# Orbiter_V3.net
KiCad netlist of a schematic drawn in EAGLE
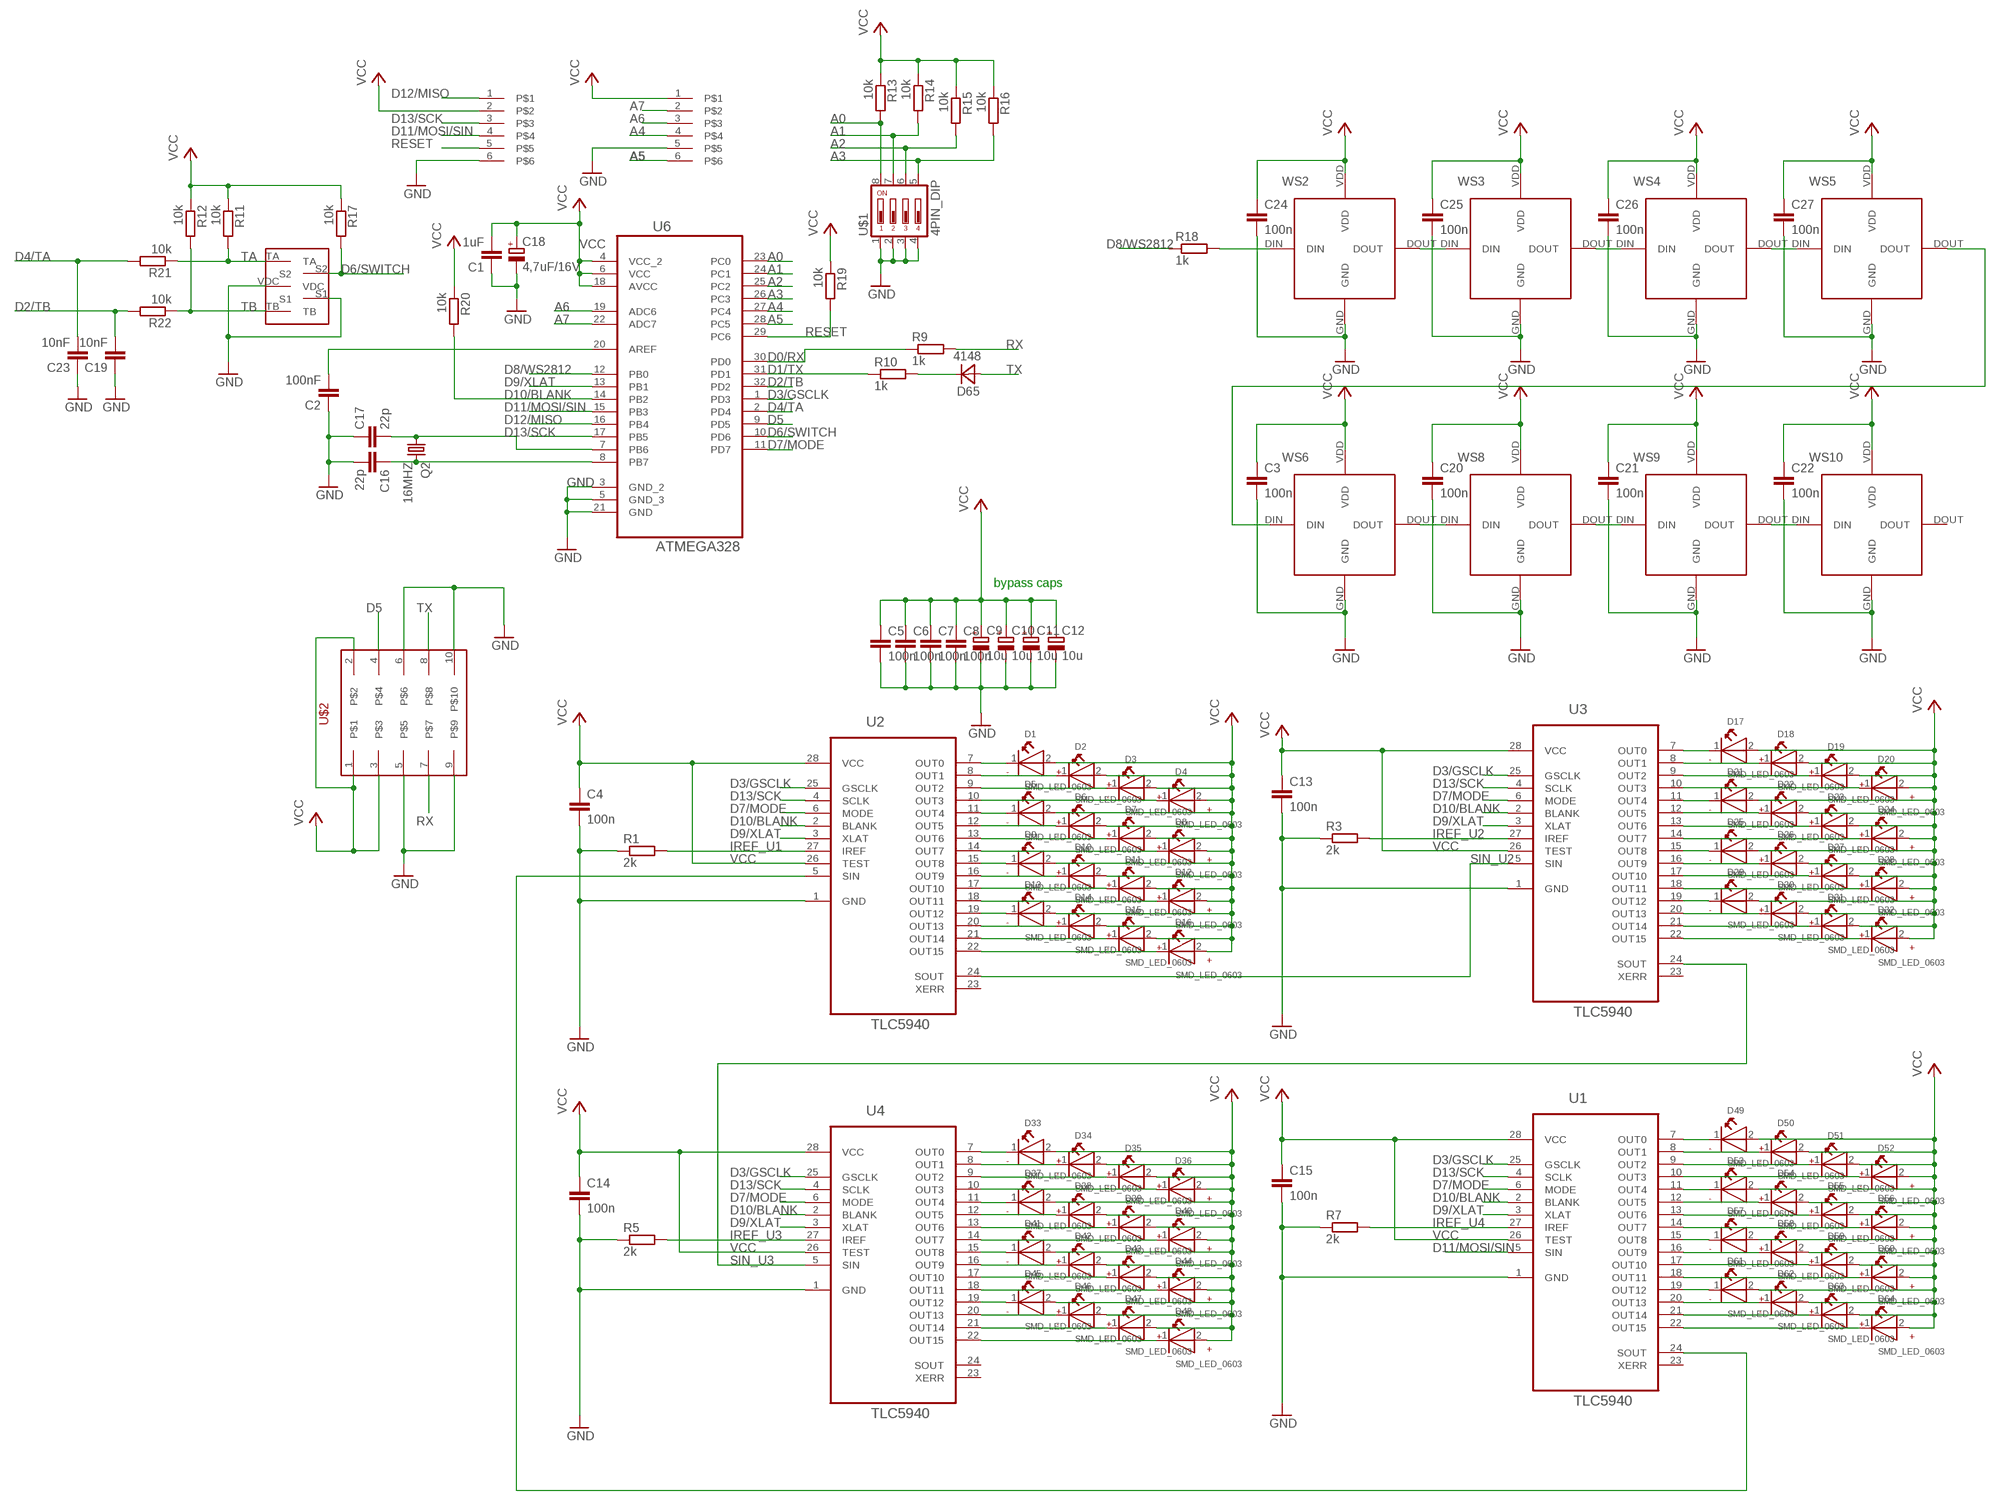
[diagram p0: schematic, sheet 1]

(export (version "E")
  (design (tool "Eeschema 10.0.6"))
  (components
    (comp (ref "C1")
      (value "1uF")
      (footprint "eagle-import:C0603")
      (libsource (lib "eagle-import") (part "KONDENSATOR_0603"))
    )
    (comp (ref "C2")
      (value "100nF")
      (footprint "eagle-import:C0603")
      (libsource (lib "eagle-import") (part "KONDENSATOR_0603"))
    )
    (comp (ref "C3")
      (value "100n")
      (footprint "eagle-import:C0603")
      (libsource (lib "eagle-import") (part "KONDENSATOR_0603"))
    )
    (comp (ref "C4")
      (value "100n")
      (footprint "eagle-import:C0603")
      (libsource (lib "eagle-import") (part "KONDENSATOR_0603"))
    )
    (comp (ref "C5")
      (value "100n")
      (footprint "eagle-import:C0603")
      (libsource (lib "eagle-import") (part "KONDENSATOR_0603"))
    )
    (comp (ref "C6")
      (value "100n")
      (footprint "eagle-import:C0603")
      (libsource (lib "eagle-import") (part "KONDENSATOR_0603"))
    )
    (comp (ref "C7")
      (value "100n")
      (footprint "eagle-import:C0603")
      (libsource (lib "eagle-import") (part "KONDENSATOR_0603"))
    )
    (comp (ref "C8")
      (value "100n")
      (footprint "eagle-import:C0603")
      (libsource (lib "eagle-import") (part "KONDENSATOR_0603"))
    )
    (comp (ref "C9")
      (value "10u")
      (footprint "eagle-import:153CLV-0605")
      (libsource (lib "eagle-import") (part "SMD_ELCTROLYTIC"))
    )
    (comp (ref "C10")
      (value "10u")
      (footprint "eagle-import:153CLV-0605")
      (libsource (lib "eagle-import") (part "SMD_ELCTROLYTIC"))
    )
    (comp (ref "C11")
      (value "10u")
      (footprint "eagle-import:153CLV-0605")
      (libsource (lib "eagle-import") (part "SMD_ELCTROLYTIC"))
    )
    (comp (ref "C12")
      (value "10u")
      (footprint "eagle-import:153CLV-0605")
      (libsource (lib "eagle-import") (part "SMD_ELCTROLYTIC"))
    )
    (comp (ref "C13")
      (value "100n")
      (footprint "eagle-import:C0603")
      (libsource (lib "eagle-import") (part "KONDENSATOR_0603"))
    )
    (comp (ref "C14")
      (value "100n")
      (footprint "eagle-import:C0603")
      (libsource (lib "eagle-import") (part "KONDENSATOR_0603"))
    )
    (comp (ref "C15")
      (value "100n")
      (footprint "eagle-import:C0603")
      (libsource (lib "eagle-import") (part "KONDENSATOR_0603"))
    )
    (comp (ref "C16")
      (value "22p")
      (footprint "eagle-import:C0603")
      (libsource (lib "eagle-import") (part "KONDENSATOR_0603"))
    )
    (comp (ref "C17")
      (value "22p")
      (footprint "eagle-import:C0603")
      (libsource (lib "eagle-import") (part "KONDENSATOR_0603"))
    )
    (comp (ref "C18")
      (value "4,7uF/16V")
      (footprint "eagle-import:153CLV-0605")
      (libsource (lib "eagle-import") (part "SMD_ELCTROLYTIC"))
    )
    (comp (ref "C19")
      (value "10nF")
      (footprint "eagle-import:C0603")
      (libsource (lib "eagle-import") (part "KONDENSATOR_0603"))
    )
    (comp (ref "C20")
      (value "100n")
      (footprint "eagle-import:C0603")
      (libsource (lib "eagle-import") (part "KONDENSATOR_0603"))
    )
    (comp (ref "C21")
      (value "100n")
      (footprint "eagle-import:C0603")
      (libsource (lib "eagle-import") (part "KONDENSATOR_0603"))
    )
    (comp (ref "C22")
      (value "100n")
      (footprint "eagle-import:C0603")
      (libsource (lib "eagle-import") (part "KONDENSATOR_0603"))
    )
    (comp (ref "C23")
      (value "10nF")
      (footprint "eagle-import:C0603")
      (libsource (lib "eagle-import") (part "KONDENSATOR_0603"))
    )
    (comp (ref "C24")
      (value "100n")
      (footprint "eagle-import:C0603")
      (libsource (lib "eagle-import") (part "KONDENSATOR_0603"))
    )
    (comp (ref "C25")
      (value "100n")
      (footprint "eagle-import:C0603")
      (libsource (lib "eagle-import") (part "KONDENSATOR_0603"))
    )
    (comp (ref "C26")
      (value "100n")
      (footprint "eagle-import:C0603")
      (libsource (lib "eagle-import") (part "KONDENSATOR_0603"))
    )
    (comp (ref "C27")
      (value "100n")
      (footprint "eagle-import:C0603")
      (libsource (lib "eagle-import") (part "KONDENSATOR_0603"))
    )
    (comp (ref "D1")
      (value "SMD_LED_0603")
      (footprint "eagle-import:WL-SMCW_0603")
      (libsource (lib "eagle-import") (part "SMD_LED_0603"))
    )
    (comp (ref "D2")
      (value "SMD_LED_0603")
      (footprint "eagle-import:WL-SMCW_0603")
      (libsource (lib "eagle-import") (part "SMD_LED_0603"))
    )
    (comp (ref "D3")
      (value "SMD_LED_0603")
      (footprint "eagle-import:WL-SMCW_0603")
      (libsource (lib "eagle-import") (part "SMD_LED_0603"))
    )
    (comp (ref "D4")
      (value "SMD_LED_0603")
      (footprint "eagle-import:WL-SMCW_0603")
      (libsource (lib "eagle-import") (part "SMD_LED_0603"))
    )
    (comp (ref "D5")
      (value "SMD_LED_0603")
      (footprint "eagle-import:WL-SMCW_0603")
      (libsource (lib "eagle-import") (part "SMD_LED_0603"))
    )
    (comp (ref "D6")
      (value "SMD_LED_0603")
      (footprint "eagle-import:WL-SMCW_0603")
      (libsource (lib "eagle-import") (part "SMD_LED_0603"))
    )
    (comp (ref "D7")
      (value "SMD_LED_0603")
      (footprint "eagle-import:WL-SMCW_0603")
      (libsource (lib "eagle-import") (part "SMD_LED_0603"))
    )
    (comp (ref "D8")
      (value "SMD_LED_0603")
      (footprint "eagle-import:WL-SMCW_0603")
      (libsource (lib "eagle-import") (part "SMD_LED_0603"))
    )
    (comp (ref "D9")
      (value "SMD_LED_0603")
      (footprint "eagle-import:WL-SMCW_0603")
      (libsource (lib "eagle-import") (part "SMD_LED_0603"))
    )
    (comp (ref "D10")
      (value "SMD_LED_0603")
      (footprint "eagle-import:WL-SMCW_0603")
      (libsource (lib "eagle-import") (part "SMD_LED_0603"))
    )
    (comp (ref "D11")
      (value "SMD_LED_0603")
      (footprint "eagle-import:WL-SMCW_0603")
      (libsource (lib "eagle-import") (part "SMD_LED_0603"))
    )
    (comp (ref "D12")
      (value "SMD_LED_0603")
      (footprint "eagle-import:WL-SMCW_0603")
      (libsource (lib "eagle-import") (part "SMD_LED_0603"))
    )
    (comp (ref "D13")
      (value "SMD_LED_0603")
      (footprint "eagle-import:WL-SMCW_0603")
      (libsource (lib "eagle-import") (part "SMD_LED_0603"))
    )
    (comp (ref "D14")
      (value "SMD_LED_0603")
      (footprint "eagle-import:WL-SMCW_0603")
      (libsource (lib "eagle-import") (part "SMD_LED_0603"))
    )
    (comp (ref "D15")
      (value "SMD_LED_0603")
      (footprint "eagle-import:WL-SMCW_0603")
      (libsource (lib "eagle-import") (part "SMD_LED_0603"))
    )
    (comp (ref "D16")
      (value "SMD_LED_0603")
      (footprint "eagle-import:WL-SMCW_0603")
      (libsource (lib "eagle-import") (part "SMD_LED_0603"))
    )
    (comp (ref "D17")
      (value "SMD_LED_0603")
      (footprint "eagle-import:WL-SMCW_0603")
      (libsource (lib "eagle-import") (part "SMD_LED_0603"))
    )
    (comp (ref "D18")
      (value "SMD_LED_0603")
      (footprint "eagle-import:WL-SMCW_0603")
      (libsource (lib "eagle-import") (part "SMD_LED_0603"))
    )
    (comp (ref "D19")
      (value "SMD_LED_0603")
      (footprint "eagle-import:WL-SMCW_0603")
      (libsource (lib "eagle-import") (part "SMD_LED_0603"))
    )
    (comp (ref "D20")
      (value "SMD_LED_0603")
      (footprint "eagle-import:WL-SMCW_0603")
      (libsource (lib "eagle-import") (part "SMD_LED_0603"))
    )
    (comp (ref "D21")
      (value "SMD_LED_0603")
      (footprint "eagle-import:WL-SMCW_0603")
      (libsource (lib "eagle-import") (part "SMD_LED_0603"))
    )
    (comp (ref "D22")
      (value "SMD_LED_0603")
      (footprint "eagle-import:WL-SMCW_0603")
      (libsource (lib "eagle-import") (part "SMD_LED_0603"))
    )
    (comp (ref "D23")
      (value "SMD_LED_0603")
      (footprint "eagle-import:WL-SMCW_0603")
      (libsource (lib "eagle-import") (part "SMD_LED_0603"))
    )
    (comp (ref "D24")
      (value "SMD_LED_0603")
      (footprint "eagle-import:WL-SMCW_0603")
      (libsource (lib "eagle-import") (part "SMD_LED_0603"))
    )
    (comp (ref "D25")
      (value "SMD_LED_0603")
      (footprint "eagle-import:WL-SMCW_0603")
      (libsource (lib "eagle-import") (part "SMD_LED_0603"))
    )
    (comp (ref "D26")
      (value "SMD_LED_0603")
      (footprint "eagle-import:WL-SMCW_0603")
      (libsource (lib "eagle-import") (part "SMD_LED_0603"))
    )
    (comp (ref "D27")
      (value "SMD_LED_0603")
      (footprint "eagle-import:WL-SMCW_0603")
      (libsource (lib "eagle-import") (part "SMD_LED_0603"))
    )
    (comp (ref "D28")
      (value "SMD_LED_0603")
      (footprint "eagle-import:WL-SMCW_0603")
      (libsource (lib "eagle-import") (part "SMD_LED_0603"))
    )
    (comp (ref "D29")
      (value "SMD_LED_0603")
      (footprint "eagle-import:WL-SMCW_0603")
      (libsource (lib "eagle-import") (part "SMD_LED_0603"))
    )
    (comp (ref "D30")
      (value "SMD_LED_0603")
      (footprint "eagle-import:WL-SMCW_0603")
      (libsource (lib "eagle-import") (part "SMD_LED_0603"))
    )
    (comp (ref "D31")
      (value "SMD_LED_0603")
      (footprint "eagle-import:WL-SMCW_0603")
      (libsource (lib "eagle-import") (part "SMD_LED_0603"))
    )
    (comp (ref "D32")
      (value "SMD_LED_0603")
      (footprint "eagle-import:WL-SMCW_0603")
      (libsource (lib "eagle-import") (part "SMD_LED_0603"))
    )
    (comp (ref "D33")
      (value "SMD_LED_0603")
      (footprint "eagle-import:WL-SMCW_0603")
      (libsource (lib "eagle-import") (part "SMD_LED_0603"))
    )
    (comp (ref "D34")
      (value "SMD_LED_0603")
      (footprint "eagle-import:WL-SMCW_0603")
      (libsource (lib "eagle-import") (part "SMD_LED_0603"))
    )
    (comp (ref "D35")
      (value "SMD_LED_0603")
      (footprint "eagle-import:WL-SMCW_0603")
      (libsource (lib "eagle-import") (part "SMD_LED_0603"))
    )
    (comp (ref "D36")
      (value "SMD_LED_0603")
      (footprint "eagle-import:WL-SMCW_0603")
      (libsource (lib "eagle-import") (part "SMD_LED_0603"))
    )
    (comp (ref "D37")
      (value "SMD_LED_0603")
      (footprint "eagle-import:WL-SMCW_0603")
      (libsource (lib "eagle-import") (part "SMD_LED_0603"))
    )
    (comp (ref "D38")
      (value "SMD_LED_0603")
      (footprint "eagle-import:WL-SMCW_0603")
      (libsource (lib "eagle-import") (part "SMD_LED_0603"))
    )
    (comp (ref "D39")
      (value "SMD_LED_0603")
      (footprint "eagle-import:WL-SMCW_0603")
      (libsource (lib "eagle-import") (part "SMD_LED_0603"))
    )
    (comp (ref "D40")
      (value "SMD_LED_0603")
      (footprint "eagle-import:WL-SMCW_0603")
      (libsource (lib "eagle-import") (part "SMD_LED_0603"))
    )
    (comp (ref "D41")
      (value "SMD_LED_0603")
      (footprint "eagle-import:WL-SMCW_0603")
      (libsource (lib "eagle-import") (part "SMD_LED_0603"))
    )
    (comp (ref "D42")
      (value "SMD_LED_0603")
      (footprint "eagle-import:WL-SMCW_0603")
      (libsource (lib "eagle-import") (part "SMD_LED_0603"))
    )
    (comp (ref "D43")
      (value "SMD_LED_0603")
      (footprint "eagle-import:WL-SMCW_0603")
      (libsource (lib "eagle-import") (part "SMD_LED_0603"))
    )
    (comp (ref "D44")
      (value "SMD_LED_0603")
      (footprint "eagle-import:WL-SMCW_0603")
      (libsource (lib "eagle-import") (part "SMD_LED_0603"))
    )
    (comp (ref "D45")
      (value "SMD_LED_0603")
      (footprint "eagle-import:WL-SMCW_0603")
      (libsource (lib "eagle-import") (part "SMD_LED_0603"))
    )
    (comp (ref "D46")
      (value "SMD_LED_0603")
      (footprint "eagle-import:WL-SMCW_0603")
      (libsource (lib "eagle-import") (part "SMD_LED_0603"))
    )
    (comp (ref "D47")
      (value "SMD_LED_0603")
      (footprint "eagle-import:WL-SMCW_0603")
      (libsource (lib "eagle-import") (part "SMD_LED_0603"))
    )
    (comp (ref "D48")
      (value "SMD_LED_0603")
      (footprint "eagle-import:WL-SMCW_0603")
      (libsource (lib "eagle-import") (part "SMD_LED_0603"))
    )
    (comp (ref "D49")
      (value "SMD_LED_0603")
      (footprint "eagle-import:WL-SMCW_0603")
      (libsource (lib "eagle-import") (part "SMD_LED_0603"))
    )
    (comp (ref "D50")
      (value "SMD_LED_0603")
      (footprint "eagle-import:WL-SMCW_0603")
      (libsource (lib "eagle-import") (part "SMD_LED_0603"))
    )
    (comp (ref "D51")
      (value "SMD_LED_0603")
      (footprint "eagle-import:WL-SMCW_0603")
      (libsource (lib "eagle-import") (part "SMD_LED_0603"))
    )
    (comp (ref "D52")
      (value "SMD_LED_0603")
      (footprint "eagle-import:WL-SMCW_0603")
      (libsource (lib "eagle-import") (part "SMD_LED_0603"))
    )
    (comp (ref "D53")
      (value "SMD_LED_0603")
      (footprint "eagle-import:WL-SMCW_0603")
      (libsource (lib "eagle-import") (part "SMD_LED_0603"))
    )
    (comp (ref "D54")
      (value "SMD_LED_0603")
      (footprint "eagle-import:WL-SMCW_0603")
      (libsource (lib "eagle-import") (part "SMD_LED_0603"))
    )
    (comp (ref "D55")
      (value "SMD_LED_0603")
      (footprint "eagle-import:WL-SMCW_0603")
      (libsource (lib "eagle-import") (part "SMD_LED_0603"))
    )
    (comp (ref "D56")
      (value "SMD_LED_0603")
      (footprint "eagle-import:WL-SMCW_0603")
      (libsource (lib "eagle-import") (part "SMD_LED_0603"))
    )
    (comp (ref "D57")
      (value "SMD_LED_0603")
      (footprint "eagle-import:WL-SMCW_0603")
      (libsource (lib "eagle-import") (part "SMD_LED_0603"))
    )
    (comp (ref "D58")
      (value "SMD_LED_0603")
      (footprint "eagle-import:WL-SMCW_0603")
      (libsource (lib "eagle-import") (part "SMD_LED_0603"))
    )
    (comp (ref "D59")
      (value "SMD_LED_0603")
      (footprint "eagle-import:WL-SMCW_0603")
      (libsource (lib "eagle-import") (part "SMD_LED_0603"))
    )
    (comp (ref "D60")
      (value "SMD_LED_0603")
      (footprint "eagle-import:WL-SMCW_0603")
      (libsource (lib "eagle-import") (part "SMD_LED_0603"))
    )
    (comp (ref "D61")
      (value "SMD_LED_0603")
      (footprint "eagle-import:WL-SMCW_0603")
      (libsource (lib "eagle-import") (part "SMD_LED_0603"))
    )
    (comp (ref "D62")
      (value "SMD_LED_0603")
      (footprint "eagle-import:WL-SMCW_0603")
      (libsource (lib "eagle-import") (part "SMD_LED_0603"))
    )
    (comp (ref "D63")
      (value "SMD_LED_0603")
      (footprint "eagle-import:WL-SMCW_0603")
      (libsource (lib "eagle-import") (part "SMD_LED_0603"))
    )
    (comp (ref "D64")
      (value "SMD_LED_0603")
      (footprint "eagle-import:WL-SMCW_0603")
      (libsource (lib "eagle-import") (part "SMD_LED_0603"))
    )
    (comp (ref "D65")
      (value "4148")
      (footprint "eagle-import:SOD323-R")
      (libsource (lib "eagle-import") (part "4148_SOD323"))
    )
    (comp (ref "Q2")
      (value "16MHZ")
      (footprint "eagle-import:SM49")
      (libsource (lib "eagle-import") (part "CRYSTAL_SM49"))
    )
    (comp (ref "R1")
      (value "2k")
      (footprint "eagle-import:R0805")
      (libsource (lib "eagle-import") (part "WIDERSTAND_0805R0805"))
    )
    (comp (ref "R3")
      (value "2k")
      (footprint "eagle-import:R0805")
      (libsource (lib "eagle-import") (part "WIDERSTAND_0805R0805"))
    )
    (comp (ref "R5")
      (value "2k")
      (footprint "eagle-import:R0805")
      (libsource (lib "eagle-import") (part "WIDERSTAND_0805R0805"))
    )
    (comp (ref "R7")
      (value "2k")
      (footprint "eagle-import:R0805")
      (libsource (lib "eagle-import") (part "WIDERSTAND_0805R0805"))
    )
    (comp (ref "R9")
      (value "1k")
      (footprint "eagle-import:R0805")
      (libsource (lib "eagle-import") (part "WIDERSTAND_0805R0805"))
    )
    (comp (ref "R10")
      (value "1k")
      (footprint "eagle-import:R0805")
      (libsource (lib "eagle-import") (part "WIDERSTAND_0805R0805"))
    )
    (comp (ref "R11")
      (value "10k")
      (footprint "eagle-import:R0805")
      (libsource (lib "eagle-import") (part "WIDERSTAND_0805R0805"))
    )
    (comp (ref "R12")
      (value "10k")
      (footprint "eagle-import:R0805")
      (libsource (lib "eagle-import") (part "WIDERSTAND_0805R0805"))
    )
    (comp (ref "R13")
      (value "10k")
      (footprint "eagle-import:R0805")
      (libsource (lib "eagle-import") (part "WIDERSTAND_0805R0805"))
    )
    (comp (ref "R14")
      (value "10k")
      (footprint "eagle-import:R0805")
      (libsource (lib "eagle-import") (part "WIDERSTAND_0805R0805"))
    )
    (comp (ref "R15")
      (value "10k")
      (footprint "eagle-import:R0805")
      (libsource (lib "eagle-import") (part "WIDERSTAND_0805R0805"))
    )
    (comp (ref "R16")
      (value "10k")
      (footprint "eagle-import:R0805")
      (libsource (lib "eagle-import") (part "WIDERSTAND_0805R0805"))
    )
    (comp (ref "R17")
      (value "10k")
      (footprint "eagle-import:R0805")
      (libsource (lib "eagle-import") (part "WIDERSTAND_0805R0805"))
    )
    (comp (ref "R18")
      (value "1k")
      (footprint "eagle-import:R0805")
      (libsource (lib "eagle-import") (part "WIDERSTAND_0805R0805"))
    )
    (comp (ref "R19")
      (value "10k")
      (footprint "eagle-import:R0805")
      (libsource (lib "eagle-import") (part "WIDERSTAND_0805R0805"))
    )
    (comp (ref "R20")
      (value "10k")
      (footprint "eagle-import:R0805")
      (libsource (lib "eagle-import") (part "WIDERSTAND_0805R0805"))
    )
    (comp (ref "R21")
      (value "10k")
      (footprint "eagle-import:R0805")
      (libsource (lib "eagle-import") (part "WIDERSTAND_0805R0805"))
    )
    (comp (ref "R22")
      (value "10k")
      (footprint "eagle-import:R0805")
      (libsource (lib "eagle-import") (part "WIDERSTAND_0805R0805"))
    )
    (comp (ref "U$1")
      (value "4PIN_DIP")
      (footprint "eagle-import:CTS-219-04")
      (libsource (lib "eagle-import") (part "4PIN_DIP"))
    )
    (comp (ref "U$2")
      (value "10PIN_HEADER_SMD")
      (footprint "eagle-import:87832-10")
      (libsource (lib "eagle-import") (part "10PIN_HEADER_SMD"))
    )
    (comp (ref "U$3")
      (value "6PIN_HEADER_SMD_OPEN")
      (footprint "eagle-import:6PIN_HEADER_SMD_OPEN")
      (libsource (lib "eagle-import") (part "6PIN_HEADER_SMD_OPEN"))
    )
    (comp (ref "U$4")
      (value "BOURNS_ENCODER")
      (footprint "eagle-import:BOURNS_ENCODER_SMD")
      (libsource (lib "eagle-import") (part "BOURNS_ENCODER"))
    )
    (comp (ref "U$5")
      (value "6PIN_HEADER_SMD_OPEN")
      (footprint "eagle-import:6PIN_HEADER_SMD_OPEN")
      (libsource (lib "eagle-import") (part "6PIN_HEADER_SMD_OPEN"))
    )
    (comp (ref "U1")
      (value "TLC5940")
      (footprint "eagle-import:SOP65P640X120-29N")
      (fields (field (name "MPN") "TLC59401PWP"))
      (libsource (lib "eagle-import") (part "TLC59401PWP"))
    )
    (comp (ref "U2")
      (value "TLC5940")
      (footprint "eagle-import:SOP65P640X120-29N")
      (fields (field (name "MPN") "TLC59401PWP"))
      (libsource (lib "eagle-import") (part "TLC59401PWP"))
    )
    (comp (ref "U3")
      (value "TLC5940")
      (footprint "eagle-import:SOP65P640X120-29N")
      (fields (field (name "MPN") "TLC59401PWP"))
      (libsource (lib "eagle-import") (part "TLC59401PWP"))
    )
    (comp (ref "U4")
      (value "TLC5940")
      (footprint "eagle-import:SOP65P640X120-29N")
      (fields (field (name "MPN") "TLC59401PWP"))
      (libsource (lib "eagle-import") (part "TLC59401PWP"))
    )
    (comp (ref "U6")
      (value "ATMEGA328")
      (footprint "eagle-import:QFP80P900X900X120-32N")
      (fields (field (name "MPN") "ATMEGA328P-AU"))
      (libsource (lib "eagle-import") (part "ATMEGA328P-AU"))
    )
    (comp (ref "WS2")
      (value "WS2812")
      (footprint "eagle-import:WS2812")
      (libsource (lib "eagle-import") (part "WS2812"))
    )
    (comp (ref "WS3")
      (value "WS2812")
      (footprint "eagle-import:WS2812")
      (libsource (lib "eagle-import") (part "WS2812"))
    )
    (comp (ref "WS4")
      (value "WS2812")
      (footprint "eagle-import:WS2812")
      (libsource (lib "eagle-import") (part "WS2812"))
    )
    (comp (ref "WS5")
      (value "WS2812")
      (footprint "eagle-import:WS2812")
      (libsource (lib "eagle-import") (part "WS2812"))
    )
    (comp (ref "WS6")
      (value "WS2812")
      (footprint "eagle-import:WS2812")
      (libsource (lib "eagle-import") (part "WS2812"))
    )
    (comp (ref "WS8")
      (value "WS2812")
      (footprint "eagle-import:WS2812")
      (libsource (lib "eagle-import") (part "WS2812"))
    )
    (comp (ref "WS9")
      (value "WS2812")
      (footprint "eagle-import:WS2812")
      (libsource (lib "eagle-import") (part "WS2812"))
    )
    (comp (ref "WS10")
      (value "WS2812")
      (footprint "eagle-import:WS2812")
      (libsource (lib "eagle-import") (part "WS2812"))
    )
  )
  (nets
    (net (code "1") (name "/A0") (class "Default")
      (node (ref "R13") (pin "2") (pinfunction "2_2") (pintype "passive"))
      (node (ref "U$1") (pin "8") (pinfunction "8_8") (pintype "passive"))
      (node (ref "U6") (pin "23") (pinfunction "PC0_23") (pintype "bidirectional"))
    )
    (net (code "2") (name "/A1") (class "Default")
      (node (ref "R14") (pin "2") (pinfunction "2_2") (pintype "passive"))
      (node (ref "U$1") (pin "7") (pinfunction "7_7") (pintype "passive"))
      (node (ref "U6") (pin "24") (pinfunction "PC1_24") (pintype "bidirectional"))
    )
    (net (code "3") (name "/A2") (class "Default")
      (node (ref "R15") (pin "2") (pinfunction "2_2") (pintype "passive"))
      (node (ref "U$1") (pin "6") (pinfunction "6_6") (pintype "passive"))
      (node (ref "U6") (pin "25") (pinfunction "PC2_25") (pintype "bidirectional"))
    )
    (net (code "4") (name "/A3") (class "Default")
      (node (ref "R16") (pin "2") (pinfunction "2_2") (pintype "passive"))
      (node (ref "U$1") (pin "5") (pinfunction "5_5") (pintype "passive"))
      (node (ref "U6") (pin "26") (pinfunction "PC3_26") (pintype "bidirectional"))
    )
    (net (code "5") (name "/A4") (class "Default")
      (node (ref "U$5") (pin "4") (pinfunction "P$4_4") (pintype "bidirectional"))
      (node (ref "U6") (pin "27") (pinfunction "PC4_27") (pintype "bidirectional"))
    )
    (net (code "6") (name "/A5") (class "Default")
      (node (ref "U$5") (pin "6") (pinfunction "P$6_6") (pintype "bidirectional"))
      (node (ref "U6") (pin "28") (pinfunction "PC5_28") (pintype "bidirectional"))
    )
    (net (code "7") (name "/A6") (class "Default")
      (node (ref "U$5") (pin "3") (pinfunction "P$3_3") (pintype "bidirectional"))
      (node (ref "U6") (pin "19") (pinfunction "ADC6_19") (pintype "input"))
    )
    (net (code "8") (name "/A7") (class "Default")
      (node (ref "U$5") (pin "2") (pinfunction "P$2_2") (pintype "bidirectional"))
      (node (ref "U6") (pin "22") (pinfunction "ADC7_22") (pintype "input"))
    )
    (net (code "9") (name "/D0{slash}RX") (class "Default")
      (node (ref "R9") (pin "1") (pinfunction "1_1") (pintype "passive"))
      (node (ref "U6") (pin "30") (pinfunction "PD0_30") (pintype "bidirectional"))
    )
    (net (code "10") (name "/D1{slash}TX") (class "Default")
      (node (ref "R10") (pin "1") (pinfunction "1_1") (pintype "passive"))
      (node (ref "U6") (pin "31") (pinfunction "PD1_31") (pintype "bidirectional"))
    )
    (net (code "11") (name "/D2{slash}TB") (class "Default")
      (node (ref "C19") (pin "2") (pinfunction "2_2") (pintype "passive"))
      (node (ref "R22") (pin "2") (pinfunction "2_2") (pintype "passive"))
      (node (ref "U6") (pin "32") (pinfunction "PD2_32") (pintype "bidirectional"))
    )
    (net (code "12") (name "/D3{slash}GSCLK") (class "Default")
      (node (ref "U1") (pin "25") (pinfunction "GSCLK_25") (pintype "input"))
      (node (ref "U2") (pin "25") (pinfunction "GSCLK_25") (pintype "input"))
      (node (ref "U3") (pin "25") (pinfunction "GSCLK_25") (pintype "input"))
      (node (ref "U4") (pin "25") (pinfunction "GSCLK_25") (pintype "input"))
      (node (ref "U6") (pin "1") (pinfunction "PD3_1") (pintype "bidirectional"))
    )
    (net (code "13") (name "/D4{slash}TA") (class "Default")
      (node (ref "C23") (pin "2") (pinfunction "2_2") (pintype "passive"))
      (node (ref "R21") (pin "2") (pinfunction "2_2") (pintype "passive"))
      (node (ref "U6") (pin "2") (pinfunction "PD4_2") (pintype "bidirectional"))
    )
    (net (code "14") (name "/D5") (class "Default")
      (node (ref "U$2") (pin "4") (pinfunction "P$4_4") (pintype "bidirectional"))
      (node (ref "U6") (pin "9") (pinfunction "PD5_9") (pintype "bidirectional"))
    )
    (net (code "15") (name "/D6{slash}SWITCH") (class "Default")
      (node (ref "R17") (pin "2") (pinfunction "2_2") (pintype "passive"))
      (node (ref "U$4") (pin "S2") (pinfunction "S2_S2") (pintype "bidirectional"))
      (node (ref "U6") (pin "10") (pinfunction "PD6_10") (pintype "bidirectional"))
    )
    (net (code "16") (name "/D7{slash}MODE") (class "Default")
      (node (ref "U1") (pin "6") (pinfunction "MODE_6") (pintype "input"))
      (node (ref "U2") (pin "6") (pinfunction "MODE_6") (pintype "input"))
      (node (ref "U3") (pin "6") (pinfunction "MODE_6") (pintype "input"))
      (node (ref "U4") (pin "6") (pinfunction "MODE_6") (pintype "input"))
      (node (ref "U6") (pin "11") (pinfunction "PD7_11") (pintype "bidirectional"))
    )
    (net (code "17") (name "/D8{slash}WS2812") (class "Default")
      (node (ref "R18") (pin "1") (pinfunction "1_1") (pintype "passive"))
      (node (ref "U6") (pin "12") (pinfunction "PB0_12") (pintype "bidirectional"))
    )
    (net (code "18") (name "/D9{slash}XLAT") (class "Default")
      (node (ref "U1") (pin "3") (pinfunction "XLAT_3") (pintype "input"))
      (node (ref "U2") (pin "3") (pinfunction "XLAT_3") (pintype "input"))
      (node (ref "U3") (pin "3") (pinfunction "XLAT_3") (pintype "input"))
      (node (ref "U4") (pin "3") (pinfunction "XLAT_3") (pintype "input"))
      (node (ref "U6") (pin "13") (pinfunction "PB1_13") (pintype "bidirectional"))
    )
    (net (code "19") (name "/D10{slash}BLANK") (class "Default")
      (node (ref "R20") (pin "2") (pinfunction "2_2") (pintype "passive"))
      (node (ref "U1") (pin "2") (pinfunction "BLANK_2") (pintype "input"))
      (node (ref "U2") (pin "2") (pinfunction "BLANK_2") (pintype "input"))
      (node (ref "U3") (pin "2") (pinfunction "BLANK_2") (pintype "input"))
      (node (ref "U4") (pin "2") (pinfunction "BLANK_2") (pintype "input"))
      (node (ref "U6") (pin "14") (pinfunction "PB2_14") (pintype "bidirectional"))
    )
    (net (code "20") (name "/D11{slash}MOSI{slash}SIN") (class "Default")
      (node (ref "U$3") (pin "4") (pinfunction "P$4_4") (pintype "bidirectional"))
      (node (ref "U1") (pin "5") (pinfunction "SIN_5") (pintype "input"))
      (node (ref "U6") (pin "15") (pinfunction "PB3_15") (pintype "bidirectional"))
    )
    (net (code "21") (name "/D12{slash}MISO") (class "Default")
      (node (ref "U$3") (pin "1") (pinfunction "P$1_1") (pintype "bidirectional"))
      (node (ref "U6") (pin "16") (pinfunction "PB4_16") (pintype "bidirectional"))
    )
    (net (code "22") (name "/D13{slash}SCK") (class "Default")
      (node (ref "U$3") (pin "3") (pinfunction "P$3_3") (pintype "bidirectional"))
      (node (ref "U1") (pin "4") (pinfunction "SCLK_4") (pintype "input"))
      (node (ref "U2") (pin "4") (pinfunction "SCLK_4") (pintype "input"))
      (node (ref "U3") (pin "4") (pinfunction "SCLK_4") (pintype "input"))
      (node (ref "U4") (pin "4") (pinfunction "SCLK_4") (pintype "input"))
      (node (ref "U6") (pin "17") (pinfunction "PB5_17") (pintype "bidirectional"))
    )
    (net (code "23") (name "/IREF_U1") (class "Default")
      (node (ref "R1") (pin "2") (pinfunction "2_2") (pintype "passive"))
      (node (ref "U2") (pin "27") (pinfunction "IREF_27") (pintype "input"))
    )
    (net (code "24") (name "/IREF_U2") (class "Default")
      (node (ref "R3") (pin "2") (pinfunction "2_2") (pintype "passive"))
      (node (ref "U3") (pin "27") (pinfunction "IREF_27") (pintype "input"))
    )
    (net (code "25") (name "/IREF_U3") (class "Default")
      (node (ref "R5") (pin "2") (pinfunction "2_2") (pintype "passive"))
      (node (ref "U4") (pin "27") (pinfunction "IREF_27") (pintype "input"))
    )
    (net (code "26") (name "/IREF_U4") (class "Default")
      (node (ref "R7") (pin "2") (pinfunction "2_2") (pintype "passive"))
      (node (ref "U1") (pin "27") (pinfunction "IREF_27") (pintype "input"))
    )
    (net (code "27") (name "/RESET") (class "Default")
      (node (ref "R19") (pin "2") (pinfunction "2_2") (pintype "passive"))
      (node (ref "U$3") (pin "5") (pinfunction "P$5_5") (pintype "bidirectional"))
      (node (ref "U6") (pin "29") (pinfunction "PC6_29") (pintype "bidirectional"))
    )
    (net (code "28") (name "/RX") (class "Default")
      (node (ref "R9") (pin "2") (pinfunction "2_2") (pintype "passive"))
      (node (ref "U$2") (pin "7") (pinfunction "P$7_7") (pintype "bidirectional"))
    )
    (net (code "29") (name "/SIN_U2") (class "Default")
      (node (ref "U2") (pin "24") (pinfunction "SOUT_24") (pintype "output"))
      (node (ref "U3") (pin "5") (pinfunction "SIN_5") (pintype "input"))
    )
    (net (code "30") (name "/SIN_U3") (class "Default")
      (node (ref "U3") (pin "24") (pinfunction "SOUT_24") (pintype "output"))
      (node (ref "U4") (pin "5") (pinfunction "SIN_5") (pintype "input"))
    )
    (net (code "31") (name "/TA") (class "Default")
      (node (ref "R11") (pin "2") (pinfunction "2_2") (pintype "passive"))
      (node (ref "R21") (pin "1") (pinfunction "1_1") (pintype "passive"))
      (node (ref "U$4") (pin "TA") (pinfunction "TA_TA") (pintype "bidirectional"))
    )
    (net (code "32") (name "/TB") (class "Default")
      (node (ref "R12") (pin "2") (pinfunction "2_2") (pintype "passive"))
      (node (ref "R22") (pin "1") (pinfunction "1_1") (pintype "passive"))
      (node (ref "U$4") (pin "TB") (pinfunction "TB_TB") (pintype "bidirectional"))
    )
    (net (code "33") (name "/TX") (class "Default")
      (node (ref "D65") (pin "A") (pinfunction "A_A") (pintype "passive"))
      (node (ref "U$2") (pin "8") (pinfunction "P$8_8") (pintype "bidirectional"))
    )
    (net (code "34") (name "GND") (class "Default")
      (node (ref "C1") (pin "1") (pinfunction "1_1") (pintype "passive"))
      (node (ref "C10") (pin "-") (pinfunction "-_-") (pintype "passive"))
      (node (ref "C11") (pin "-") (pinfunction "-_-") (pintype "passive"))
      (node (ref "C12") (pin "-") (pinfunction "-_-") (pintype "passive"))
      (node (ref "C13") (pin "2") (pinfunction "2_2") (pintype "passive"))
      (node (ref "C14") (pin "2") (pinfunction "2_2") (pintype "passive"))
      (node (ref "C15") (pin "2") (pinfunction "2_2") (pintype "passive"))
      (node (ref "C16") (pin "2") (pinfunction "2_2") (pintype "passive"))
      (node (ref "C17") (pin "1") (pinfunction "1_1") (pintype "passive"))
      (node (ref "C18") (pin "-") (pinfunction "-_-") (pintype "passive"))
      (node (ref "C19") (pin "1") (pinfunction "1_1") (pintype "passive"))
      (node (ref "C2") (pin "1") (pinfunction "1_1") (pintype "passive"))
      (node (ref "C20") (pin "2") (pinfunction "2_2") (pintype "passive"))
      (node (ref "C21") (pin "2") (pinfunction "2_2") (pintype "passive"))
      (node (ref "C22") (pin "2") (pinfunction "2_2") (pintype "passive"))
      (node (ref "C23") (pin "1") (pinfunction "1_1") (pintype "passive"))
      (node (ref "C24") (pin "2") (pinfunction "2_2") (pintype "passive"))
      (node (ref "C25") (pin "2") (pinfunction "2_2") (pintype "passive"))
      (node (ref "C26") (pin "2") (pinfunction "2_2") (pintype "passive"))
      (node (ref "C27") (pin "2") (pinfunction "2_2") (pintype "passive"))
      (node (ref "C3") (pin "2") (pinfunction "2_2") (pintype "passive"))
      (node (ref "C4") (pin "2") (pinfunction "2_2") (pintype "passive"))
      (node (ref "C5") (pin "2") (pinfunction "2_2") (pintype "passive"))
      (node (ref "C6") (pin "2") (pinfunction "2_2") (pintype "passive"))
      (node (ref "C7") (pin "2") (pinfunction "2_2") (pintype "passive"))
      (node (ref "C8") (pin "2") (pinfunction "2_2") (pintype "passive"))
      (node (ref "C9") (pin "-") (pinfunction "-_-") (pintype "passive"))
      (node (ref "R1") (pin "1") (pinfunction "1_1") (pintype "passive"))
      (node (ref "R3") (pin "1") (pinfunction "1_1") (pintype "passive"))
      (node (ref "R5") (pin "1") (pinfunction "1_1") (pintype "passive"))
      (node (ref "R7") (pin "1") (pinfunction "1_1") (pintype "passive"))
      (node (ref "U$1") (pin "1") (pinfunction "1_1") (pintype "passive"))
      (node (ref "U$1") (pin "2") (pinfunction "2_2") (pintype "passive"))
      (node (ref "U$1") (pin "3") (pinfunction "3_3") (pintype "passive"))
      (node (ref "U$1") (pin "4") (pinfunction "4_4") (pintype "passive"))
      (node (ref "U$2") (pin "10") (pinfunction "P$10_10") (pintype "bidirectional"))
      (node (ref "U$2") (pin "5") (pinfunction "P$5_5") (pintype "bidirectional"))
      (node (ref "U$2") (pin "6") (pinfunction "P$6_6") (pintype "bidirectional"))
      (node (ref "U$2") (pin "9") (pinfunction "P$9_9") (pintype "bidirectional"))
      (node (ref "U$3") (pin "6") (pinfunction "P$6_6") (pintype "bidirectional"))
      (node (ref "U$4") (pin "S1") (pinfunction "S1_S1") (pintype "bidirectional"))
      (node (ref "U$4") (pin "VDC") (pinfunction "VDC_VDC") (pintype "bidirectional"))
      (node (ref "U$5") (pin "5") (pinfunction "P$5_5") (pintype "bidirectional"))
      (node (ref "U1") (pin "1") (pinfunction "GND_1") (pintype "passive"))
      (node (ref "U2") (pin "1") (pinfunction "GND_1") (pintype "passive"))
      (node (ref "U3") (pin "1") (pinfunction "GND_1") (pintype "passive"))
      (node (ref "U4") (pin "1") (pinfunction "GND_1") (pintype "passive"))
      (node (ref "U6") (pin "21") (pinfunction "GND_21") (pintype "passive"))
      (node (ref "U6") (pin "3") (pinfunction "GND_2_3") (pintype "passive"))
      (node (ref "U6") (pin "5") (pinfunction "GND_3_5") (pintype "passive"))
      (node (ref "WS10") (pin "GND") (pinfunction "GND_GND") (pintype "bidirectional"))
      (node (ref "WS2") (pin "GND") (pinfunction "GND_GND") (pintype "bidirectional"))
      (node (ref "WS3") (pin "GND") (pinfunction "GND_GND") (pintype "bidirectional"))
      (node (ref "WS4") (pin "GND") (pinfunction "GND_GND") (pintype "bidirectional"))
      (node (ref "WS5") (pin "GND") (pinfunction "GND_GND") (pintype "bidirectional"))
      (node (ref "WS6") (pin "GND") (pinfunction "GND_GND") (pintype "bidirectional"))
      (node (ref "WS8") (pin "GND") (pinfunction "GND_GND") (pintype "bidirectional"))
      (node (ref "WS9") (pin "GND") (pinfunction "GND_GND") (pintype "bidirectional"))
    )
    (net (code "35") (name "Net-(D1--)") (class "Default")
      (node (ref "D1") (pin "1") (pinfunction "-_1") (pintype "passive"))
      (node (ref "U2") (pin "7") (pinfunction "OUT0_7") (pintype "output"))
    )
    (net (code "36") (name "Net-(D2--)") (class "Default")
      (node (ref "D2") (pin "1") (pinfunction "-_1") (pintype "passive"))
      (node (ref "U2") (pin "8") (pinfunction "OUT1_8") (pintype "output"))
    )
    (net (code "37") (name "Net-(D3--)") (class "Default")
      (node (ref "D3") (pin "1") (pinfunction "-_1") (pintype "passive"))
      (node (ref "U2") (pin "9") (pinfunction "OUT2_9") (pintype "output"))
    )
    (net (code "38") (name "Net-(D4--)") (class "Default")
      (node (ref "D4") (pin "1") (pinfunction "-_1") (pintype "passive"))
      (node (ref "U2") (pin "10") (pinfunction "OUT3_10") (pintype "output"))
    )
    (net (code "39") (name "Net-(D5--)") (class "Default")
      (node (ref "D5") (pin "1") (pinfunction "-_1") (pintype "passive"))
      (node (ref "U2") (pin "11") (pinfunction "OUT4_11") (pintype "output"))
    )
    (net (code "40") (name "Net-(D6--)") (class "Default")
      (node (ref "D6") (pin "1") (pinfunction "-_1") (pintype "passive"))
      (node (ref "U2") (pin "12") (pinfunction "OUT5_12") (pintype "output"))
    )
    (net (code "41") (name "Net-(D7--)") (class "Default")
      (node (ref "D7") (pin "1") (pinfunction "-_1") (pintype "passive"))
      (node (ref "U2") (pin "13") (pinfunction "OUT6_13") (pintype "output"))
    )
    (net (code "42") (name "Net-(D8--)") (class "Default")
      (node (ref "D8") (pin "1") (pinfunction "-_1") (pintype "passive"))
      (node (ref "U2") (pin "14") (pinfunction "OUT7_14") (pintype "output"))
    )
    (net (code "43") (name "Net-(D9--)") (class "Default")
      (node (ref "D9") (pin "1") (pinfunction "-_1") (pintype "passive"))
      (node (ref "U2") (pin "15") (pinfunction "OUT8_15") (pintype "output"))
    )
    (net (code "44") (name "Net-(D10--)") (class "Default")
      (node (ref "D10") (pin "1") (pinfunction "-_1") (pintype "passive"))
      (node (ref "U2") (pin "16") (pinfunction "OUT9_16") (pintype "output"))
    )
    (net (code "45") (name "Net-(D11--)") (class "Default")
      (node (ref "D11") (pin "1") (pinfunction "-_1") (pintype "passive"))
      (node (ref "U2") (pin "17") (pinfunction "OUT10_17") (pintype "output"))
    )
    (net (code "46") (name "Net-(D12--)") (class "Default")
      (node (ref "D12") (pin "1") (pinfunction "-_1") (pintype "passive"))
      (node (ref "U2") (pin "18") (pinfunction "OUT11_18") (pintype "output"))
    )
    (net (code "47") (name "Net-(D13--)") (class "Default")
      (node (ref "D13") (pin "1") (pinfunction "-_1") (pintype "passive"))
      (node (ref "U2") (pin "19") (pinfunction "OUT12_19") (pintype "output"))
    )
    (net (code "48") (name "Net-(D14--)") (class "Default")
      (node (ref "D14") (pin "1") (pinfunction "-_1") (pintype "passive"))
      (node (ref "U2") (pin "20") (pinfunction "OUT13_20") (pintype "output"))
    )
    (net (code "49") (name "Net-(D15--)") (class "Default")
      (node (ref "D15") (pin "1") (pinfunction "-_1") (pintype "passive"))
      (node (ref "U2") (pin "21") (pinfunction "OUT14_21") (pintype "output"))
    )
    (net (code "50") (name "Net-(D16--)") (class "Default")
      (node (ref "D16") (pin "1") (pinfunction "-_1") (pintype "passive"))
      (node (ref "U2") (pin "22") (pinfunction "OUT15_22") (pintype "output"))
    )
    (net (code "51") (name "Net-(D17--)") (class "Default")
      (node (ref "D17") (pin "1") (pinfunction "-_1") (pintype "passive"))
      (node (ref "U3") (pin "7") (pinfunction "OUT0_7") (pintype "output"))
    )
    (net (code "52") (name "Net-(D18--)") (class "Default")
      (node (ref "D18") (pin "1") (pinfunction "-_1") (pintype "passive"))
      (node (ref "U3") (pin "8") (pinfunction "OUT1_8") (pintype "output"))
    )
    (net (code "53") (name "Net-(D19--)") (class "Default")
      (node (ref "D19") (pin "1") (pinfunction "-_1") (pintype "passive"))
      (node (ref "U3") (pin "9") (pinfunction "OUT2_9") (pintype "output"))
    )
    (net (code "54") (name "Net-(D20--)") (class "Default")
      (node (ref "D20") (pin "1") (pinfunction "-_1") (pintype "passive"))
      (node (ref "U3") (pin "10") (pinfunction "OUT3_10") (pintype "output"))
    )
    (net (code "55") (name "Net-(D21--)") (class "Default")
      (node (ref "D21") (pin "1") (pinfunction "-_1") (pintype "passive"))
      (node (ref "U3") (pin "11") (pinfunction "OUT4_11") (pintype "output"))
    )
    (net (code "56") (name "Net-(D22--)") (class "Default")
      (node (ref "D22") (pin "1") (pinfunction "-_1") (pintype "passive"))
      (node (ref "U3") (pin "12") (pinfunction "OUT5_12") (pintype "output"))
    )
    (net (code "57") (name "Net-(D23--)") (class "Default")
      (node (ref "D23") (pin "1") (pinfunction "-_1") (pintype "passive"))
      (node (ref "U3") (pin "13") (pinfunction "OUT6_13") (pintype "output"))
    )
    (net (code "58") (name "Net-(D24--)") (class "Default")
      (node (ref "D24") (pin "1") (pinfunction "-_1") (pintype "passive"))
      (node (ref "U3") (pin "14") (pinfunction "OUT7_14") (pintype "output"))
    )
    (net (code "59") (name "Net-(D25--)") (class "Default")
      (node (ref "D25") (pin "1") (pinfunction "-_1") (pintype "passive"))
      (node (ref "U3") (pin "15") (pinfunction "OUT8_15") (pintype "output"))
    )
    (net (code "60") (name "Net-(D26--)") (class "Default")
      (node (ref "D26") (pin "1") (pinfunction "-_1") (pintype "passive"))
      (node (ref "U3") (pin "16") (pinfunction "OUT9_16") (pintype "output"))
    )
    (net (code "61") (name "Net-(D27--)") (class "Default")
      (node (ref "D27") (pin "1") (pinfunction "-_1") (pintype "passive"))
      (node (ref "U3") (pin "17") (pinfunction "OUT10_17") (pintype "output"))
    )
    (net (code "62") (name "Net-(D28--)") (class "Default")
      (node (ref "D28") (pin "1") (pinfunction "-_1") (pintype "passive"))
      (node (ref "U3") (pin "18") (pinfunction "OUT11_18") (pintype "output"))
    )
    (net (code "63") (name "Net-(D29--)") (class "Default")
      (node (ref "D29") (pin "1") (pinfunction "-_1") (pintype "passive"))
      (node (ref "U3") (pin "19") (pinfunction "OUT12_19") (pintype "output"))
    )
    (net (code "64") (name "Net-(D30--)") (class "Default")
      (node (ref "D30") (pin "1") (pinfunction "-_1") (pintype "passive"))
      (node (ref "U3") (pin "20") (pinfunction "OUT13_20") (pintype "output"))
    )
    (net (code "65") (name "Net-(D31--)") (class "Default")
      (node (ref "D31") (pin "1") (pinfunction "-_1") (pintype "passive"))
      (node (ref "U3") (pin "21") (pinfunction "OUT14_21") (pintype "output"))
    )
    (net (code "66") (name "Net-(D32--)") (class "Default")
      (node (ref "D32") (pin "1") (pinfunction "-_1") (pintype "passive"))
      (node (ref "U3") (pin "22") (pinfunction "OUT15_22") (pintype "output"))
    )
    (net (code "67") (name "Net-(D33--)") (class "Default")
      (node (ref "D33") (pin "1") (pinfunction "-_1") (pintype "passive"))
      (node (ref "U4") (pin "7") (pinfunction "OUT0_7") (pintype "output"))
    )
    (net (code "68") (name "Net-(D34--)") (class "Default")
      (node (ref "D34") (pin "1") (pinfunction "-_1") (pintype "passive"))
      (node (ref "U4") (pin "8") (pinfunction "OUT1_8") (pintype "output"))
    )
    (net (code "69") (name "Net-(D35--)") (class "Default")
      (node (ref "D35") (pin "1") (pinfunction "-_1") (pintype "passive"))
      (node (ref "U4") (pin "9") (pinfunction "OUT2_9") (pintype "output"))
    )
    (net (code "70") (name "Net-(D36--)") (class "Default")
      (node (ref "D36") (pin "1") (pinfunction "-_1") (pintype "passive"))
      (node (ref "U4") (pin "10") (pinfunction "OUT3_10") (pintype "output"))
    )
    (net (code "71") (name "Net-(D37--)") (class "Default")
      (node (ref "D37") (pin "1") (pinfunction "-_1") (pintype "passive"))
      (node (ref "U4") (pin "11") (pinfunction "OUT4_11") (pintype "output"))
    )
    (net (code "72") (name "Net-(D38--)") (class "Default")
      (node (ref "D38") (pin "1") (pinfunction "-_1") (pintype "passive"))
      (node (ref "U4") (pin "12") (pinfunction "OUT5_12") (pintype "output"))
    )
    (net (code "73") (name "Net-(D39--)") (class "Default")
      (node (ref "D39") (pin "1") (pinfunction "-_1") (pintype "passive"))
      (node (ref "U4") (pin "13") (pinfunction "OUT6_13") (pintype "output"))
    )
    (net (code "74") (name "Net-(D40--)") (class "Default")
      (node (ref "D40") (pin "1") (pinfunction "-_1") (pintype "passive"))
      (node (ref "U4") (pin "14") (pinfunction "OUT7_14") (pintype "output"))
    )
    (net (code "75") (name "Net-(D41--)") (class "Default")
      (node (ref "D41") (pin "1") (pinfunction "-_1") (pintype "passive"))
      (node (ref "U4") (pin "15") (pinfunction "OUT8_15") (pintype "output"))
    )
    (net (code "76") (name "Net-(D42--)") (class "Default")
      (node (ref "D42") (pin "1") (pinfunction "-_1") (pintype "passive"))
      (node (ref "U4") (pin "16") (pinfunction "OUT9_16") (pintype "output"))
    )
    (net (code "77") (name "Net-(D43--)") (class "Default")
      (node (ref "D43") (pin "1") (pinfunction "-_1") (pintype "passive"))
      (node (ref "U4") (pin "17") (pinfunction "OUT10_17") (pintype "output"))
    )
    (net (code "78") (name "Net-(D44--)") (class "Default")
      (node (ref "D44") (pin "1") (pinfunction "-_1") (pintype "passive"))
      (node (ref "U4") (pin "18") (pinfunction "OUT11_18") (pintype "output"))
    )
    (net (code "79") (name "Net-(D45--)") (class "Default")
      (node (ref "D45") (pin "1") (pinfunction "-_1") (pintype "passive"))
      (node (ref "U4") (pin "19") (pinfunction "OUT12_19") (pintype "output"))
    )
    (net (code "80") (name "Net-(D46--)") (class "Default")
      (node (ref "D46") (pin "1") (pinfunction "-_1") (pintype "passive"))
      (node (ref "U4") (pin "20") (pinfunction "OUT13_20") (pintype "output"))
    )
    (net (code "81") (name "Net-(D47--)") (class "Default")
      (node (ref "D47") (pin "1") (pinfunction "-_1") (pintype "passive"))
      (node (ref "U4") (pin "21") (pinfunction "OUT14_21") (pintype "output"))
    )
    (net (code "82") (name "Net-(D48--)") (class "Default")
      (node (ref "D48") (pin "1") (pinfunction "-_1") (pintype "passive"))
      (node (ref "U4") (pin "22") (pinfunction "OUT15_22") (pintype "output"))
    )
    (net (code "83") (name "Net-(D49--)") (class "Default")
      (node (ref "D49") (pin "1") (pinfunction "-_1") (pintype "passive"))
      (node (ref "U1") (pin "7") (pinfunction "OUT0_7") (pintype "output"))
    )
    (net (code "84") (name "Net-(D50--)") (class "Default")
      (node (ref "D50") (pin "1") (pinfunction "-_1") (pintype "passive"))
      (node (ref "U1") (pin "8") (pinfunction "OUT1_8") (pintype "output"))
    )
    (net (code "85") (name "Net-(D51--)") (class "Default")
      (node (ref "D51") (pin "1") (pinfunction "-_1") (pintype "passive"))
      (node (ref "U1") (pin "9") (pinfunction "OUT2_9") (pintype "output"))
    )
    (net (code "86") (name "Net-(D52--)") (class "Default")
      (node (ref "D52") (pin "1") (pinfunction "-_1") (pintype "passive"))
      (node (ref "U1") (pin "10") (pinfunction "OUT3_10") (pintype "output"))
    )
    (net (code "87") (name "Net-(D53--)") (class "Default")
      (node (ref "D53") (pin "1") (pinfunction "-_1") (pintype "passive"))
      (node (ref "U1") (pin "11") (pinfunction "OUT4_11") (pintype "output"))
    )
    (net (code "88") (name "Net-(D54--)") (class "Default")
      (node (ref "D54") (pin "1") (pinfunction "-_1") (pintype "passive"))
      (node (ref "U1") (pin "12") (pinfunction "OUT5_12") (pintype "output"))
    )
    (net (code "89") (name "Net-(D55--)") (class "Default")
      (node (ref "D55") (pin "1") (pinfunction "-_1") (pintype "passive"))
      (node (ref "U1") (pin "13") (pinfunction "OUT6_13") (pintype "output"))
    )
    (net (code "90") (name "Net-(D56--)") (class "Default")
      (node (ref "D56") (pin "1") (pinfunction "-_1") (pintype "passive"))
      (node (ref "U1") (pin "14") (pinfunction "OUT7_14") (pintype "output"))
    )
    (net (code "91") (name "Net-(D57--)") (class "Default")
      (node (ref "D57") (pin "1") (pinfunction "-_1") (pintype "passive"))
      (node (ref "U1") (pin "15") (pinfunction "OUT8_15") (pintype "output"))
    )
    (net (code "92") (name "Net-(D58--)") (class "Default")
      (node (ref "D58") (pin "1") (pinfunction "-_1") (pintype "passive"))
      (node (ref "U1") (pin "16") (pinfunction "OUT9_16") (pintype "output"))
    )
    (net (code "93") (name "Net-(D59--)") (class "Default")
      (node (ref "D59") (pin "1") (pinfunction "-_1") (pintype "passive"))
      (node (ref "U1") (pin "17") (pinfunction "OUT10_17") (pintype "output"))
    )
    (net (code "94") (name "Net-(D60--)") (class "Default")
      (node (ref "D60") (pin "1") (pinfunction "-_1") (pintype "passive"))
      (node (ref "U1") (pin "18") (pinfunction "OUT11_18") (pintype "output"))
    )
    (net (code "95") (name "Net-(D61--)") (class "Default")
      (node (ref "D61") (pin "1") (pinfunction "-_1") (pintype "passive"))
      (node (ref "U1") (pin "19") (pinfunction "OUT12_19") (pintype "output"))
    )
    (net (code "96") (name "Net-(D62--)") (class "Default")
      (node (ref "D62") (pin "1") (pinfunction "-_1") (pintype "passive"))
      (node (ref "U1") (pin "20") (pinfunction "OUT13_20") (pintype "output"))
    )
    (net (code "97") (name "Net-(D63--)") (class "Default")
      (node (ref "D63") (pin "1") (pinfunction "-_1") (pintype "passive"))
      (node (ref "U1") (pin "21") (pinfunction "OUT14_21") (pintype "output"))
    )
    (net (code "98") (name "Net-(D64--)") (class "Default")
      (node (ref "D64") (pin "1") (pinfunction "-_1") (pintype "passive"))
      (node (ref "U1") (pin "22") (pinfunction "OUT15_22") (pintype "output"))
    )
    (net (code "99") (name "Net-(D65-PadC)") (class "Default")
      (node (ref "D65") (pin "C") (pinfunction "C_C") (pintype "passive"))
      (node (ref "R10") (pin "2") (pinfunction "2_2") (pintype "passive"))
    )
    (net (code "100") (name "Net-(R18-Pad2)") (class "Default")
      (node (ref "R18") (pin "2") (pinfunction "2_2") (pintype "passive"))
      (node (ref "WS2") (pin "DIN") (pinfunction "DIN_DIN") (pintype "bidirectional"))
    )
    (net (code "101") (name "Net-(U1-SOUT)") (class "Default")
      (node (ref "U1") (pin "24") (pinfunction "SOUT_24") (pintype "output"))
      (node (ref "U2") (pin "5") (pinfunction "SIN_5") (pintype "input"))
    )
    (net (code "102") (name "Net-(U6-AREF)") (class "Default")
      (node (ref "C2") (pin "2") (pinfunction "2_2") (pintype "passive"))
      (node (ref "U6") (pin "20") (pinfunction "AREF_20") (pintype "input"))
    )
    (net (code "103") (name "Net-(U6-PB6)") (class "Default")
      (node (ref "C17") (pin "2") (pinfunction "2_2") (pintype "passive"))
      (node (ref "Q2") (pin "1") (pinfunction "1_1") (pintype "passive"))
      (node (ref "U6") (pin "7") (pinfunction "PB6_7") (pintype "bidirectional"))
    )
    (net (code "104") (name "Net-(U6-PB7)") (class "Default")
      (node (ref "C16") (pin "1") (pinfunction "1_1") (pintype "passive"))
      (node (ref "Q2") (pin "2") (pinfunction "2_2") (pintype "passive"))
      (node (ref "U6") (pin "8") (pinfunction "PB7_8") (pintype "bidirectional"))
    )
    (net (code "105") (name "Net-(WS2-PadDOUT)") (class "Default")
      (node (ref "WS2") (pin "DOUT") (pinfunction "DOUT_DOUT") (pintype "bidirectional"))
      (node (ref "WS3") (pin "DIN") (pinfunction "DIN_DIN") (pintype "bidirectional"))
    )
    (net (code "106") (name "Net-(WS3-PadDOUT)") (class "Default")
      (node (ref "WS3") (pin "DOUT") (pinfunction "DOUT_DOUT") (pintype "bidirectional"))
      (node (ref "WS4") (pin "DIN") (pinfunction "DIN_DIN") (pintype "bidirectional"))
    )
    (net (code "107") (name "Net-(WS4-PadDOUT)") (class "Default")
      (node (ref "WS4") (pin "DOUT") (pinfunction "DOUT_DOUT") (pintype "bidirectional"))
      (node (ref "WS5") (pin "DIN") (pinfunction "DIN_DIN") (pintype "bidirectional"))
    )
    (net (code "108") (name "Net-(WS5-PadDOUT)") (class "Default")
      (node (ref "WS5") (pin "DOUT") (pinfunction "DOUT_DOUT") (pintype "bidirectional"))
      (node (ref "WS6") (pin "DIN") (pinfunction "DIN_DIN") (pintype "bidirectional"))
    )
    (net (code "109") (name "Net-(WS6-PadDOUT)") (class "Default")
      (node (ref "WS6") (pin "DOUT") (pinfunction "DOUT_DOUT") (pintype "bidirectional"))
      (node (ref "WS8") (pin "DIN") (pinfunction "DIN_DIN") (pintype "bidirectional"))
    )
    (net (code "110") (name "Net-(WS8-PadDOUT)") (class "Default")
      (node (ref "WS8") (pin "DOUT") (pinfunction "DOUT_DOUT") (pintype "bidirectional"))
      (node (ref "WS9") (pin "DIN") (pinfunction "DIN_DIN") (pintype "bidirectional"))
    )
    (net (code "111") (name "Net-(WS10-PadDIN)") (class "Default")
      (node (ref "WS10") (pin "DIN") (pinfunction "DIN_DIN") (pintype "bidirectional"))
      (node (ref "WS9") (pin "DOUT") (pinfunction "DOUT_DOUT") (pintype "bidirectional"))
    )
    (net (code "112") (name "VCC") (class "Default")
      (node (ref "C1") (pin "2") (pinfunction "2_2") (pintype "passive"))
      (node (ref "C10") (pin "+") (pinfunction "+_+") (pintype "passive"))
      (node (ref "C11") (pin "+") (pinfunction "+_+") (pintype "passive"))
      (node (ref "C12") (pin "+") (pinfunction "+_+") (pintype "passive"))
      (node (ref "C13") (pin "1") (pinfunction "1_1") (pintype "passive"))
      (node (ref "C14") (pin "1") (pinfunction "1_1") (pintype "passive"))
      (node (ref "C15") (pin "1") (pinfunction "1_1") (pintype "passive"))
      (node (ref "C18") (pin "+") (pinfunction "+_+") (pintype "passive"))
      (node (ref "C20") (pin "1") (pinfunction "1_1") (pintype "passive"))
      (node (ref "C21") (pin "1") (pinfunction "1_1") (pintype "passive"))
      (node (ref "C22") (pin "1") (pinfunction "1_1") (pintype "passive"))
      (node (ref "C24") (pin "1") (pinfunction "1_1") (pintype "passive"))
      (node (ref "C25") (pin "1") (pinfunction "1_1") (pintype "passive"))
      (node (ref "C26") (pin "1") (pinfunction "1_1") (pintype "passive"))
      (node (ref "C27") (pin "1") (pinfunction "1_1") (pintype "passive"))
      (node (ref "C3") (pin "1") (pinfunction "1_1") (pintype "passive"))
      (node (ref "C4") (pin "1") (pinfunction "1_1") (pintype "passive"))
      (node (ref "C5") (pin "1") (pinfunction "1_1") (pintype "passive"))
      (node (ref "C6") (pin "1") (pinfunction "1_1") (pintype "passive"))
      (node (ref "C7") (pin "1") (pinfunction "1_1") (pintype "passive"))
      (node (ref "C8") (pin "1") (pinfunction "1_1") (pintype "passive"))
      (node (ref "C9") (pin "+") (pinfunction "+_+") (pintype "passive"))
      (node (ref "D1") (pin "2") (pinfunction "+_2") (pintype "passive"))
      (node (ref "D10") (pin "2") (pinfunction "+_2") (pintype "passive"))
      (node (ref "D11") (pin "2") (pinfunction "+_2") (pintype "passive"))
      (node (ref "D12") (pin "2") (pinfunction "+_2") (pintype "passive"))
      (node (ref "D13") (pin "2") (pinfunction "+_2") (pintype "passive"))
      (node (ref "D14") (pin "2") (pinfunction "+_2") (pintype "passive"))
      (node (ref "D15") (pin "2") (pinfunction "+_2") (pintype "passive"))
      (node (ref "D16") (pin "2") (pinfunction "+_2") (pintype "passive"))
      (node (ref "D17") (pin "2") (pinfunction "+_2") (pintype "passive"))
      (node (ref "D18") (pin "2") (pinfunction "+_2") (pintype "passive"))
      (node (ref "D19") (pin "2") (pinfunction "+_2") (pintype "passive"))
      (node (ref "D2") (pin "2") (pinfunction "+_2") (pintype "passive"))
      (node (ref "D20") (pin "2") (pinfunction "+_2") (pintype "passive"))
      (node (ref "D21") (pin "2") (pinfunction "+_2") (pintype "passive"))
      (node (ref "D22") (pin "2") (pinfunction "+_2") (pintype "passive"))
      (node (ref "D23") (pin "2") (pinfunction "+_2") (pintype "passive"))
      (node (ref "D24") (pin "2") (pinfunction "+_2") (pintype "passive"))
      (node (ref "D25") (pin "2") (pinfunction "+_2") (pintype "passive"))
      (node (ref "D26") (pin "2") (pinfunction "+_2") (pintype "passive"))
      (node (ref "D27") (pin "2") (pinfunction "+_2") (pintype "passive"))
      (node (ref "D28") (pin "2") (pinfunction "+_2") (pintype "passive"))
      (node (ref "D29") (pin "2") (pinfunction "+_2") (pintype "passive"))
      (node (ref "D3") (pin "2") (pinfunction "+_2") (pintype "passive"))
      (node (ref "D30") (pin "2") (pinfunction "+_2") (pintype "passive"))
      (node (ref "D31") (pin "2") (pinfunction "+_2") (pintype "passive"))
      (node (ref "D32") (pin "2") (pinfunction "+_2") (pintype "passive"))
      (node (ref "D33") (pin "2") (pinfunction "+_2") (pintype "passive"))
      (node (ref "D34") (pin "2") (pinfunction "+_2") (pintype "passive"))
      (node (ref "D35") (pin "2") (pinfunction "+_2") (pintype "passive"))
      (node (ref "D36") (pin "2") (pinfunction "+_2") (pintype "passive"))
      (node (ref "D37") (pin "2") (pinfunction "+_2") (pintype "passive"))
      (node (ref "D38") (pin "2") (pinfunction "+_2") (pintype "passive"))
      (node (ref "D39") (pin "2") (pinfunction "+_2") (pintype "passive"))
      (node (ref "D4") (pin "2") (pinfunction "+_2") (pintype "passive"))
      (node (ref "D40") (pin "2") (pinfunction "+_2") (pintype "passive"))
      (node (ref "D41") (pin "2") (pinfunction "+_2") (pintype "passive"))
      (node (ref "D42") (pin "2") (pinfunction "+_2") (pintype "passive"))
      (node (ref "D43") (pin "2") (pinfunction "+_2") (pintype "passive"))
      (node (ref "D44") (pin "2") (pinfunction "+_2") (pintype "passive"))
      (node (ref "D45") (pin "2") (pinfunction "+_2") (pintype "passive"))
      (node (ref "D46") (pin "2") (pinfunction "+_2") (pintype "passive"))
      (node (ref "D47") (pin "2") (pinfunction "+_2") (pintype "passive"))
      (node (ref "D48") (pin "2") (pinfunction "+_2") (pintype "passive"))
      (node (ref "D49") (pin "2") (pinfunction "+_2") (pintype "passive"))
      (node (ref "D5") (pin "2") (pinfunction "+_2") (pintype "passive"))
      (node (ref "D50") (pin "2") (pinfunction "+_2") (pintype "passive"))
      (node (ref "D51") (pin "2") (pinfunction "+_2") (pintype "passive"))
      (node (ref "D52") (pin "2") (pinfunction "+_2") (pintype "passive"))
      (node (ref "D53") (pin "2") (pinfunction "+_2") (pintype "passive"))
      (node (ref "D54") (pin "2") (pinfunction "+_2") (pintype "passive"))
      (node (ref "D55") (pin "2") (pinfunction "+_2") (pintype "passive"))
      (node (ref "D56") (pin "2") (pinfunction "+_2") (pintype "passive"))
      (node (ref "D57") (pin "2") (pinfunction "+_2") (pintype "passive"))
      (node (ref "D58") (pin "2") (pinfunction "+_2") (pintype "passive"))
      (node (ref "D59") (pin "2") (pinfunction "+_2") (pintype "passive"))
      (node (ref "D6") (pin "2") (pinfunction "+_2") (pintype "passive"))
      (node (ref "D60") (pin "2") (pinfunction "+_2") (pintype "passive"))
      (node (ref "D61") (pin "2") (pinfunction "+_2") (pintype "passive"))
      (node (ref "D62") (pin "2") (pinfunction "+_2") (pintype "passive"))
      (node (ref "D63") (pin "2") (pinfunction "+_2") (pintype "passive"))
      (node (ref "D64") (pin "2") (pinfunction "+_2") (pintype "passive"))
      (node (ref "D7") (pin "2") (pinfunction "+_2") (pintype "passive"))
      (node (ref "D8") (pin "2") (pinfunction "+_2") (pintype "passive"))
      (node (ref "D9") (pin "2") (pinfunction "+_2") (pintype "passive"))
      (node (ref "R11") (pin "1") (pinfunction "1_1") (pintype "passive"))
      (node (ref "R12") (pin "1") (pinfunction "1_1") (pintype "passive"))
      (node (ref "R13") (pin "1") (pinfunction "1_1") (pintype "passive"))
      (node (ref "R14") (pin "1") (pinfunction "1_1") (pintype "passive"))
      (node (ref "R15") (pin "1") (pinfunction "1_1") (pintype "passive"))
      (node (ref "R16") (pin "1") (pinfunction "1_1") (pintype "passive"))
      (node (ref "R17") (pin "1") (pinfunction "1_1") (pintype "passive"))
      (node (ref "R19") (pin "1") (pinfunction "1_1") (pintype "passive"))
      (node (ref "R20") (pin "1") (pinfunction "1_1") (pintype "passive"))
      (node (ref "U$2") (pin "1") (pinfunction "P$1_1") (pintype "bidirectional"))
      (node (ref "U$2") (pin "2") (pinfunction "P$2_2") (pintype "bidirectional"))
      (node (ref "U$2") (pin "3") (pinfunction "P$3_3") (pintype "bidirectional"))
      (node (ref "U$3") (pin "2") (pinfunction "P$2_2") (pintype "bidirectional"))
      (node (ref "U$5") (pin "1") (pinfunction "P$1_1") (pintype "bidirectional"))
      (node (ref "U1") (pin "26") (pinfunction "TEST_26") (pintype "input"))
      (node (ref "U1") (pin "28") (pinfunction "VCC_28") (pintype "power_in"))
      (node (ref "U2") (pin "26") (pinfunction "TEST_26") (pintype "input"))
      (node (ref "U2") (pin "28") (pinfunction "VCC_28") (pintype "power_in"))
      (node (ref "U3") (pin "26") (pinfunction "TEST_26") (pintype "input"))
      (node (ref "U3") (pin "28") (pinfunction "VCC_28") (pintype "power_in"))
      (node (ref "U4") (pin "26") (pinfunction "TEST_26") (pintype "input"))
      (node (ref "U4") (pin "28") (pinfunction "VCC_28") (pintype "power_in"))
      (node (ref "U6") (pin "18") (pinfunction "AVCC_18") (pintype "power_in"))
      (node (ref "U6") (pin "4") (pinfunction "VCC_2_4") (pintype "power_in"))
      (node (ref "U6") (pin "6") (pinfunction "VCC_6") (pintype "power_in"))
      (node (ref "WS10") (pin "VDD") (pinfunction "VDD_VDD") (pintype "bidirectional"))
      (node (ref "WS2") (pin "VDD") (pinfunction "VDD_VDD") (pintype "bidirectional"))
      (node (ref "WS3") (pin "VDD") (pinfunction "VDD_VDD") (pintype "bidirectional"))
      (node (ref "WS4") (pin "VDD") (pinfunction "VDD_VDD") (pintype "bidirectional"))
      (node (ref "WS5") (pin "VDD") (pinfunction "VDD_VDD") (pintype "bidirectional"))
      (node (ref "WS6") (pin "VDD") (pinfunction "VDD_VDD") (pintype "bidirectional"))
      (node (ref "WS8") (pin "VDD") (pinfunction "VDD_VDD") (pintype "bidirectional"))
      (node (ref "WS9") (pin "VDD") (pinfunction "VDD_VDD") (pintype "bidirectional"))
    )
    (net (code "113") (name "unconnected-(U1-XERR-Pad23)") (class "Default")
      (node (ref "U1") (pin "23") (pinfunction "XERR_23") (pintype "output"))
    )
    (net (code "114") (name "unconnected-(U2-XERR-Pad23)") (class "Default")
      (node (ref "U2") (pin "23") (pinfunction "XERR_23") (pintype "output"))
    )
    (net (code "115") (name "unconnected-(U3-XERR-Pad23)") (class "Default")
      (node (ref "U3") (pin "23") (pinfunction "XERR_23") (pintype "output"))
    )
    (net (code "116") (name "unconnected-(U4-SOUT-Pad24)") (class "Default")
      (node (ref "U4") (pin "24") (pinfunction "SOUT_24") (pintype "output"))
    )
    (net (code "117") (name "unconnected-(U4-XERR-Pad23)") (class "Default")
      (node (ref "U4") (pin "23") (pinfunction "XERR_23") (pintype "output"))
    )
    (net (code "118") (name "unconnected-(WS10-PadDOUT)") (class "Default")
      (node (ref "WS10") (pin "DOUT") (pinfunction "DOUT_DOUT") (pintype "bidirectional"))
    )
  )
)
